# CyloRen-rev5_0.net
KiCad netlist of a schematic drawn in EAGLE
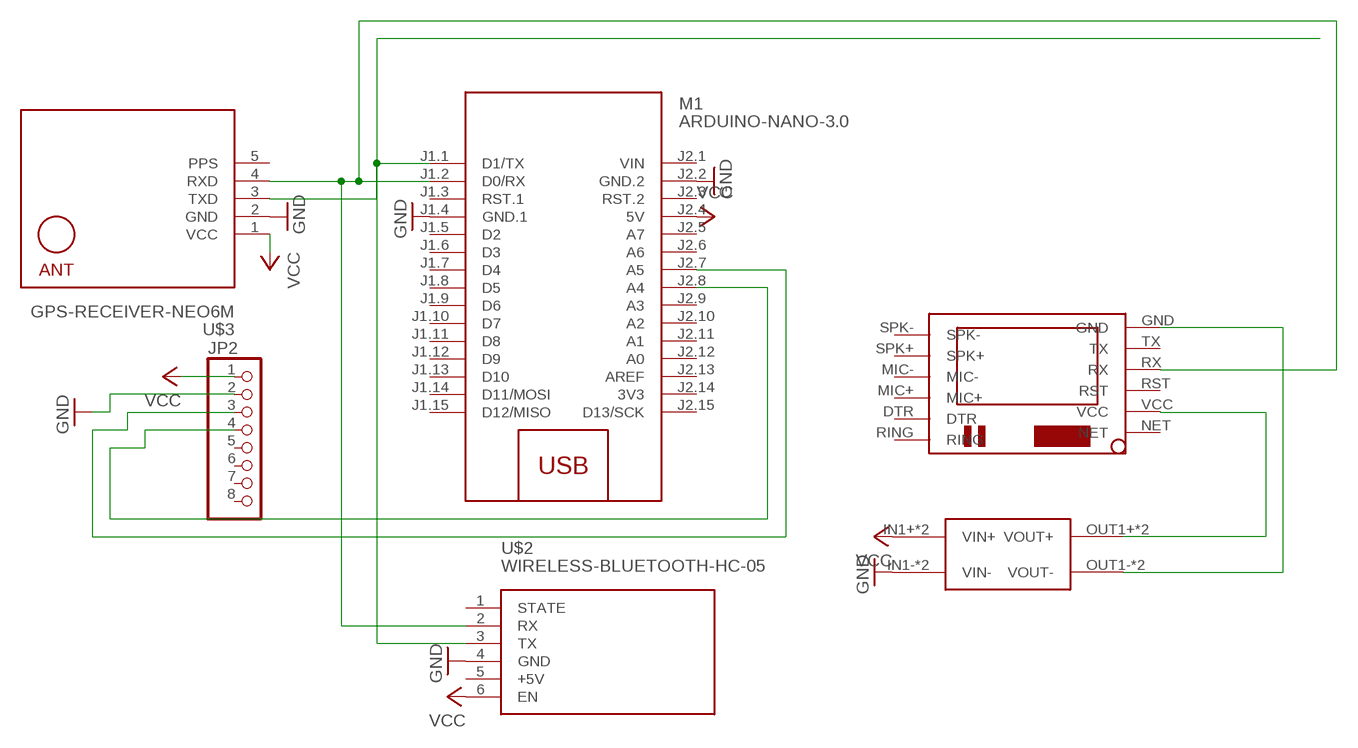
[diagram p0: schematic, sheet 1]

(export (version "E")
  (design (tool "Eeschema 10.0.6"))
  (components
    (comp (ref "JP2")
      (value "PINHD-1X8BIG")
      (footprint "eagle-import:1X08-BIG")
      (libsource (lib "eagle-import") (part "PINHD-1X8BIG"))
    )
    (comp (ref "M1")
      (value "ARDUINO-NANO-3.0")
      (footprint "eagle-import:ARDUINO-NANO-3.0")
      (libsource (lib "eagle-import") (part "ARDUINO-NANO-3.0"))
    )
    (comp (ref "U$1")
      (value "MP1584")
      (footprint "eagle-import:DC-BRICK")
      (libsource (lib "eagle-import") (part "MP1584"))
    )
    (comp (ref "U$2")
      (value "WIRELESS-BLUETOOTH-HC-05")
      (footprint "eagle-import:WIRELESS-BLUETOOTH-HC-05")
      (libsource (lib "eagle-import") (part "WIRELESS-BLUETOOTH-HC-05"))
    )
    (comp (ref "U$3")
      (value "GPS-RECEIVER-NEO6M")
      (footprint "eagle-import:GPS-RECEIVER-NEO6M")
      (libsource (lib "eagle-import") (part "GPS-RECEIVER-NEO6M"))
    )
    (comp (ref "U$4")
      (value "SIM800LMODULE")
      (footprint "eagle-import:SIM800LMODULE")
      (libsource (lib "eagle-import") (part "SIM800LMODULE"))
    )
  )
  (nets
    (net (code "1") (name "/+5V") (class "Default")
      (node (ref "U$2") (pin "5") (pinfunction "+5V_5") (pintype "power_in"))
    )
    (net (code "2") (name "/3V3") (class "Default")
      (node (ref "M1") (pin "J2.14") (pinfunction "3V3_J2.14") (pintype "power_in"))
    )
    (net (code "3") (name "/PPS") (class "Default")
      (node (ref "U$3") (pin "5") (pinfunction "PPS_5") (pintype "power_in"))
    )
    (net (code "4") (name "/VIN") (class "Default")
      (node (ref "M1") (pin "J2.1") (pinfunction "VIN_J2.1") (pintype "power_in"))
    )
    (net (code "5") (name "GND") (class "Default")
      (node (ref "JP2") (pin "2") (pinfunction "2_2") (pintype "passive"))
      (node (ref "M1") (pin "J1.4") (pinfunction "GND.1_J1.4") (pintype "power_in"))
      (node (ref "M1") (pin "J2.2") (pinfunction "GND.2_J2.2") (pintype "power_in"))
      (node (ref "U$1") (pin "IN1-") (pinfunction "VIN-_IN1-") (pintype "input"))
      (node (ref "U$1") (pin "IN2-") (pinfunction "VIN-_IN2-") (pintype "input"))
      (node (ref "U$2") (pin "4") (pinfunction "GND_4") (pintype "power_in"))
      (node (ref "U$3") (pin "2") (pinfunction "GND_2") (pintype "bidirectional"))
    )
    (net (code "6") (name "Net-(M1-A4)") (class "Default")
      (node (ref "JP2") (pin "4") (pinfunction "4_4") (pintype "passive"))
      (node (ref "M1") (pin "J2.8") (pinfunction "A4_J2.8") (pintype "bidirectional"))
    )
    (net (code "7") (name "Net-(M1-A5)") (class "Default")
      (node (ref "JP2") (pin "3") (pinfunction "3_3") (pintype "passive"))
      (node (ref "M1") (pin "J2.7") (pinfunction "A5_J2.7") (pintype "bidirectional"))
    )
    (net (code "8") (name "Net-(M1-D0{slash}RX)") (class "Default")
      (node (ref "M1") (pin "J1.2") (pinfunction "D0/RX_J1.2") (pintype "bidirectional"))
      (node (ref "U$2") (pin "2") (pinfunction "RX_2") (pintype "bidirectional"))
      (node (ref "U$3") (pin "4") (pinfunction "RXD_4") (pintype "power_in"))
      (node (ref "U$4") (pin "RX") (pinfunction "RX_RX") (pintype "bidirectional"))
    )
    (net (code "9") (name "Net-(M1-D1{slash}TX)") (class "Default")
      (node (ref "M1") (pin "J1.1") (pinfunction "D1/TX_J1.1") (pintype "bidirectional"))
      (node (ref "U$2") (pin "3") (pinfunction "TX_3") (pintype "bidirectional"))
      (node (ref "U$3") (pin "3") (pinfunction "TXD_3") (pintype "bidirectional"))
    )
    (net (code "10") (name "Net-(U$1-VOUT+-PadOUT1+)") (class "Default")
      (node (ref "U$1") (pin "OUT1+") (pinfunction "VOUT+_OUT1+") (pintype "output"))
      (node (ref "U$1") (pin "OUT2+") (pinfunction "VOUT+_OUT2+") (pintype "output"))
      (node (ref "U$4") (pin "VCC") (pinfunction "VCC_VCC") (pintype "bidirectional"))
    )
    (net (code "11") (name "Net-(U$1-VOUT--PadOUT1-)") (class "Default")
      (node (ref "U$1") (pin "OUT1-") (pinfunction "VOUT-_OUT1-") (pintype "output"))
      (node (ref "U$1") (pin "OUT2-") (pinfunction "VOUT-_OUT2-") (pintype "output"))
      (node (ref "U$4") (pin "GND") (pinfunction "GND_GND") (pintype "bidirectional"))
    )
    (net (code "12") (name "VCC") (class "Default")
      (node (ref "JP2") (pin "1") (pinfunction "1_1") (pintype "passive"))
      (node (ref "M1") (pin "J2.4") (pinfunction "5V_J2.4") (pintype "power_in"))
      (node (ref "U$1") (pin "IN1+") (pinfunction "VIN+_IN1+") (pintype "input"))
      (node (ref "U$1") (pin "IN2+") (pinfunction "VIN+_IN2+") (pintype "input"))
      (node (ref "U$2") (pin "6") (pinfunction "EN_6") (pintype "bidirectional"))
      (node (ref "U$3") (pin "1") (pinfunction "VCC_1") (pintype "bidirectional"))
    )
    (net (code "13") (name "unconnected-(JP2-Pad5)") (class "Default")
      (node (ref "JP2") (pin "5") (pinfunction "5_5") (pintype "passive"))
    )
    (net (code "14") (name "unconnected-(JP2-Pad6)") (class "Default")
      (node (ref "JP2") (pin "6") (pinfunction "6_6") (pintype "passive"))
    )
    (net (code "15") (name "unconnected-(JP2-Pad7)") (class "Default")
      (node (ref "JP2") (pin "7") (pinfunction "7_7") (pintype "passive"))
    )
    (net (code "16") (name "unconnected-(JP2-Pad8)") (class "Default")
      (node (ref "JP2") (pin "8") (pinfunction "8_8") (pintype "passive"))
    )
    (net (code "17") (name "unconnected-(M1-A0-PadJ2.12)") (class "Default")
      (node (ref "M1") (pin "J2.12") (pinfunction "A0_J2.12") (pintype "bidirectional"))
    )
    (net (code "18") (name "unconnected-(M1-A1-PadJ2.11)") (class "Default")
      (node (ref "M1") (pin "J2.11") (pinfunction "A1_J2.11") (pintype "bidirectional"))
    )
    (net (code "19") (name "unconnected-(M1-A2-PadJ2.10)") (class "Default")
      (node (ref "M1") (pin "J2.10") (pinfunction "A2_J2.10") (pintype "bidirectional"))
    )
    (net (code "20") (name "unconnected-(M1-A3-PadJ2.9)") (class "Default")
      (node (ref "M1") (pin "J2.9") (pinfunction "A3_J2.9") (pintype "bidirectional"))
    )
    (net (code "21") (name "unconnected-(M1-A6-PadJ2.6)") (class "Default")
      (node (ref "M1") (pin "J2.6") (pinfunction "A6_J2.6") (pintype "bidirectional"))
    )
    (net (code "22") (name "unconnected-(M1-A7-PadJ2.5)") (class "Default")
      (node (ref "M1") (pin "J2.5") (pinfunction "A7_J2.5") (pintype "bidirectional"))
    )
    (net (code "23") (name "unconnected-(M1-AREF-PadJ2.13)") (class "Default")
      (node (ref "M1") (pin "J2.13") (pinfunction "AREF_J2.13") (pintype "bidirectional"))
    )
    (net (code "24") (name "unconnected-(M1-D2-PadJ1.5)") (class "Default")
      (node (ref "M1") (pin "J1.5") (pinfunction "D2_J1.5") (pintype "bidirectional"))
    )
    (net (code "25") (name "unconnected-(M1-D3-PadJ1.6)") (class "Default")
      (node (ref "M1") (pin "J1.6") (pinfunction "D3_J1.6") (pintype "bidirectional"))
    )
    (net (code "26") (name "unconnected-(M1-D4-PadJ1.7)") (class "Default")
      (node (ref "M1") (pin "J1.7") (pinfunction "D4_J1.7") (pintype "bidirectional"))
    )
    (net (code "27") (name "unconnected-(M1-D5-PadJ1.8)") (class "Default")
      (node (ref "M1") (pin "J1.8") (pinfunction "D5_J1.8") (pintype "bidirectional"))
    )
    (net (code "28") (name "unconnected-(M1-D6-PadJ1.9)") (class "Default")
      (node (ref "M1") (pin "J1.9") (pinfunction "D6_J1.9") (pintype "bidirectional"))
    )
    (net (code "29") (name "unconnected-(M1-D7-PadJ1.10)") (class "Default")
      (node (ref "M1") (pin "J1.10") (pinfunction "D7_J1.10") (pintype "bidirectional"))
    )
    (net (code "30") (name "unconnected-(M1-D8-PadJ1.11)") (class "Default")
      (node (ref "M1") (pin "J1.11") (pinfunction "D8_J1.11") (pintype "bidirectional"))
    )
    (net (code "31") (name "unconnected-(M1-D9-PadJ1.12)") (class "Default")
      (node (ref "M1") (pin "J1.12") (pinfunction "D9_J1.12") (pintype "bidirectional"))
    )
    (net (code "32") (name "unconnected-(M1-D10-PadJ1.13)") (class "Default")
      (node (ref "M1") (pin "J1.13") (pinfunction "D10_J1.13") (pintype "bidirectional"))
    )
    (net (code "33") (name "unconnected-(M1-D11{slash}MOSI-PadJ1.14)") (class "Default")
      (node (ref "M1") (pin "J1.14") (pinfunction "D11/MOSI_J1.14") (pintype "bidirectional"))
    )
    (net (code "34") (name "unconnected-(M1-D12{slash}MISO-PadJ1.15)") (class "Default")
      (node (ref "M1") (pin "J1.15") (pinfunction "D12/MISO_J1.15") (pintype "bidirectional"))
    )
    (net (code "35") (name "unconnected-(M1-D13{slash}SCK-PadJ2.15)") (class "Default")
      (node (ref "M1") (pin "J2.15") (pinfunction "D13/SCK_J2.15") (pintype "bidirectional"))
    )
    (net (code "36") (name "unconnected-(M1-RST.1-PadJ1.3)") (class "Default")
      (node (ref "M1") (pin "J1.3") (pinfunction "RST.1_J1.3") (pintype "bidirectional"))
    )
    (net (code "37") (name "unconnected-(M1-RST.2-PadJ2.3)") (class "Default")
      (node (ref "M1") (pin "J2.3") (pinfunction "RST.2_J2.3") (pintype "bidirectional"))
    )
    (net (code "38") (name "unconnected-(U$2-STATE-Pad1)") (class "Default")
      (node (ref "U$2") (pin "1") (pinfunction "STATE_1") (pintype "bidirectional"))
    )
    (net (code "39") (name "unconnected-(U$4-PadDTR)") (class "Default")
      (node (ref "U$4") (pin "DTR") (pinfunction "DTR_DTR") (pintype "bidirectional"))
    )
    (net (code "40") (name "unconnected-(U$4-PadMIC+)") (class "Default")
      (node (ref "U$4") (pin "MIC+") (pinfunction "MIC+_MIC+") (pintype "bidirectional"))
    )
    (net (code "41") (name "unconnected-(U$4-PadMIC-)") (class "Default")
      (node (ref "U$4") (pin "MIC-") (pinfunction "MIC-_MIC-") (pintype "bidirectional"))
    )
    (net (code "42") (name "unconnected-(U$4-PadNET)") (class "Default")
      (node (ref "U$4") (pin "NET") (pinfunction "NET_NET") (pintype "bidirectional"))
    )
    (net (code "43") (name "unconnected-(U$4-PadRING)") (class "Default")
      (node (ref "U$4") (pin "RING") (pinfunction "RING_RING") (pintype "bidirectional"))
    )
    (net (code "44") (name "unconnected-(U$4-PadRST)") (class "Default")
      (node (ref "U$4") (pin "RST") (pinfunction "RST_RST") (pintype "bidirectional"))
    )
    (net (code "45") (name "unconnected-(U$4-PadSPK+)") (class "Default")
      (node (ref "U$4") (pin "SPK+") (pinfunction "SPK+_SPK+") (pintype "bidirectional"))
    )
    (net (code "46") (name "unconnected-(U$4-PadSPK-)") (class "Default")
      (node (ref "U$4") (pin "SPK-") (pinfunction "SPK-_SPK-") (pintype "bidirectional"))
    )
    (net (code "47") (name "unconnected-(U$4-PadTX)") (class "Default")
      (node (ref "U$4") (pin "TX") (pinfunction "TX_TX") (pintype "bidirectional"))
    )
  )
)
